# Power_2.net
KiCad netlist of a schematic drawn in Altium Designer
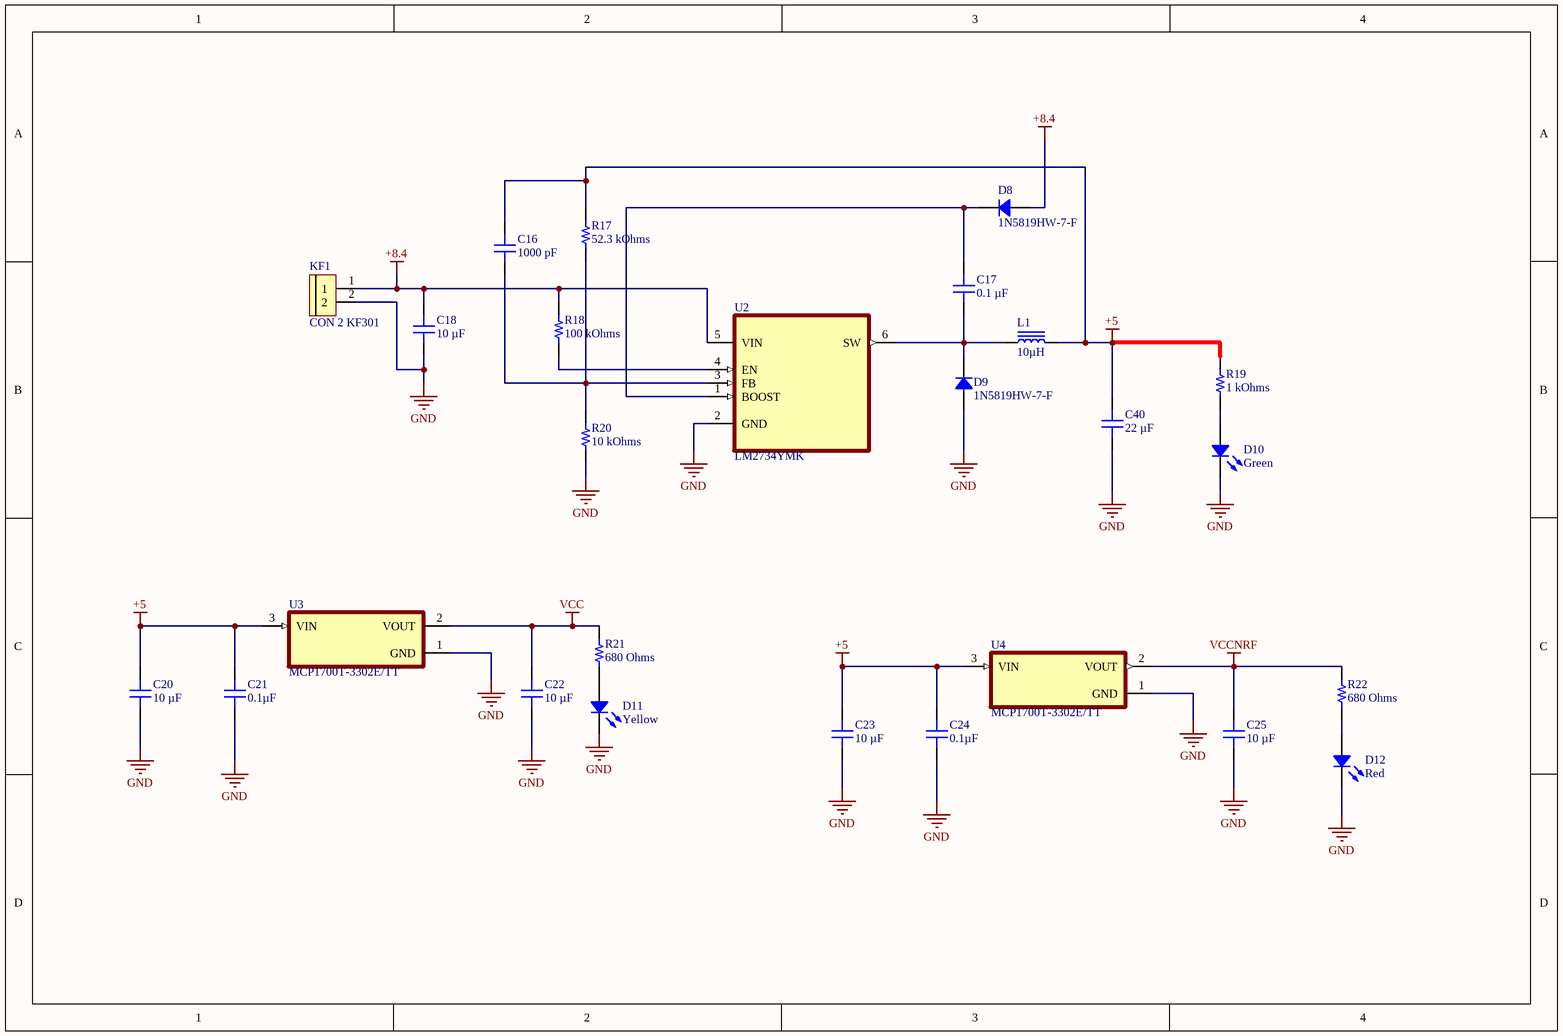
[diagram p0: Power_2.SchDoc]

(export (version "E")
  (design (tool "Eeschema 10.0.6"))
  (components
    (comp (ref "C16")
      (value "1000 pF")
      (footprint "CAP 0603_1608")
      (description "CAP CER 1000PF 10V X7R 0603")
      (fields
        (field (name "PART NUMBER") "VJ0603Y102KXQCW1BC")
        (field (name "MANUFACTURER") "Vishay Vitramon")
      )
      (libsource (lib "Celestial Altium Library - altium_library") (part "Capacitor"))
    )
    (comp (ref "C17")
      (value "0.1 µF")
      (footprint "CAP 0603_1608")
      (description "CAP CER 0.1UF 10V X7R 0603")
      (fields
        (field (name "PART NUMBER") "CX0603MRX7R6BB104")
        (field (name "MANUFACTURER") "PulseLarsen Antennas")
      )
      (libsource (lib "Celestial Altium Library - altium_library") (part "Capacitor"))
    )
    (comp (ref "C18")
      (value "10 µF")
      (footprint "CAP 0805_2012")
      (description "CAP CER 10UF 16V X5R 0805")
      (fields
        (field (name "PART NUMBER") "CL21A106KOQNNWE")
        (field (name "MANUFACTURER") "Samsung Electro-Mechanics")
      )
      (libsource (lib "Celestial Altium Library - altium_library") (part "Capacitor"))
    )
    (comp (ref "C20")
      (value "10 µF")
      (footprint "CAP 0805_2012")
      (description "CAP CER 10UF 16V X5R 0805")
      (fields
        (field (name "PART NUMBER") "CL21A106KOQNNNG")
        (field (name "MANUFACTURER") "Samsung Electro-Mechanics")
      )
      (libsource (lib "Celestial Altium Library - altium_library") (part "Capacitor"))
    )
    (comp (ref "C21")
      (value "0.1µF")
      (footprint "CAP 0603_1608")
      (description "CAP CER 0.1UF 10V X7R 0603")
      (fields (field (name "PART NUMBER") "LD03ZC104KAB2A") (field (name "MANUFACTURER") "AVX Corporation"))
      (libsource (lib "Celestial Altium Library - altium_library") (part "Capacitor"))
    )
    (comp (ref "C22")
      (value "10 µF")
      (footprint "CAP 0603_1608")
      (description "CAP CER 10UF 10V X6S 0603")
      (fields (field (name "PART NUMBER") "KGM15CS61A106MT") (field (name "MANUFACTURER") "KYOCERA AVX"))
      (libsource (lib "Celestial Altium Library - altium_library") (part "Capacitor"))
    )
    (comp (ref "C23")
      (value "10 µF")
      (footprint "CAP 0805_2012")
      (description "CAP CER 10UF 16V X5R 0805")
      (fields
        (field (name "PART NUMBER") "CL21A106KOQNNNG")
        (field (name "MANUFACTURER") "Samsung Electro-Mechanics")
      )
      (libsource (lib "Celestial Altium Library - altium_library") (part "Capacitor"))
    )
    (comp (ref "C24")
      (value "0.1µF")
      (footprint "CAP 0603_1608")
      (description "CAP CER 0.1UF 16V X7R 0603")
      (fields (field (name "PART NUMBER") "0603YC104JAZ2A") (field (name "MANUFACTURER") "AVX Corporation"))
      (libsource (lib "Celestial Altium Library - altium_library") (part "Capacitor"))
    )
    (comp (ref "C25")
      (value "10 µF")
      (footprint "CAP 0603_1608")
      (description "CAP CER 10UF 10V X6S 0603")
      (fields (field (name "PART NUMBER") "KGM15CS61A106MT") (field (name "MANUFACTURER") "KYOCERA AVX"))
      (libsource (lib "Celestial Altium Library - altium_library") (part "Capacitor"))
    )
    (comp (ref "C40")
      (value "22 µF")
      (footprint "CAP 0805_2012")
      (description "CAP CER 22UF 10V X5R 0805")
      (fields
        (field (name "PART NUMBER") "C2012X5R1A226M125AE")
        (field (name "MANUFACTURER") "TDK Corporation")
      )
      (libsource (lib "Celestial Altium Library - altium_library") (part "Capacitor"))
    )
    (comp (ref "D8")
      (value "1N5819HW-7-F")
      (footprint "SOD-123")
      (description "DIODE SCHOTTKY 40V 1A SOD123")
      (fields (field (name "MANUFACTURER") "Diodes Incorporated"))
      (libsource (lib "Celestial Altium Library - altium_library") (part "Diode"))
    )
    (comp (ref "D9")
      (value "1N5819HW-7-F")
      (footprint "SOD-123")
      (description "DIODE SCHOTTKY 40V 1A SOD123")
      (fields (field (name "MANUFACTURER") "Diodes Incorporated"))
      (libsource (lib "Celestial Altium Library - altium_library") (part "Diode"))
    )
    (comp (ref "D10")
      (value "Green")
      (footprint "LED 0603_1608 GREEN")
      (description "LED GREEN CLEAR 0603 SMD")
      (fields (field (name "PART NUMBER") "QBLP601-IG") (field (name "MANUFACTURER") "QT Brightek (QTB)"))
      (libsource (lib "Celestial Altium Library - altium_library") (part "LED"))
    )
    (comp (ref "D11")
      (value "Yellow")
      (footprint "LED 0603_1608 YELLOW")
      (description "LED YELLOW CLEAR 0603 SMD")
      (fields
        (field (name "PART NUMBER") "VAOL-S6YP4")
        (field (name "MANUFACTURER") "Visual Communications Company - VCC")
      )
      (libsource (lib "Celestial Altium Library - altium_library") (part "LED"))
    )
    (comp (ref "D12")
      (value "Red")
      (footprint "LED 0603_1608 RED")
      (description "LED RED CLEAR 0603 SMD")
      (fields
        (field (name "PART NUMBER") "B18W1URO-20C000114U1930")
        (field (name "MANUFACTURER") "Harvatek Corporation")
      )
      (libsource (lib "Celestial Altium Library - altium_library") (part "LED"))
    )
    (comp (ref "KF1")
      (value "CON 2 KF301")
      (footprint "Con 2 KF301 5.08")
      (description "Cắm")
      (libsource (lib "Connector") (part "CON 2 KF301"))
    )
    (comp (ref "L1")
      (value "10µH")
      (footprint "TDK SLF7032")
      (description "FIXED IND 10UH 1.4A 63.6 MOHM")
      (fields
        (field (name "PART NUMBER") "SLF7032T-100M1R4-2PF")
        (field (name "MANUFACTURER") "TDK Corporation")
      )
      (libsource (lib "Celestial Altium Library - altium_library") (part "Inductor"))
    )
    (comp (ref "R17")
      (value "52.3 kOhms")
      (footprint "RES 0603_1608")
      (description "RES 52.3K OHM 1% 1/10W 0603")
      (fields
        (field (name "PART NUMBER") "RMEF0603FT52K3")
        (field (name "MANUFACTURER") "Stackpole Electronics Inc")
      )
      (libsource (lib "Celestial Altium Library - altium_library") (part "Resistor"))
    )
    (comp (ref "R18")
      (value "100 kOhms")
      (footprint "RES 0603_1608")
      (description "RES 100K OHM 0.1% 1/10W 0603")
      (fields (field (name "PART NUMBER") "TNPW0603100KBXEN") (field (name "MANUFACTURER") "Vishay Dale"))
      (libsource (lib "Celestial Altium Library - altium_library") (part "Resistor"))
    )
    (comp (ref "R19")
      (value "1 kOhms")
      (footprint "RES 0603_1608")
      (description "RES SMD 1K OHM 0.1% 1/10W 0603")
      (fields (field (name "PART NUMBER") "RG1608V-102-B-T5") (field (name "MANUFACTURER") "Susumu"))
      (libsource (lib "Celestial Altium Library - altium_library") (part "Resistor"))
    )
    (comp (ref "R20")
      (value "10 kOhms")
      (footprint "RES 0603_1608")
      (description "RES SMD 10K OHM 0.1% 1/16W 0603")
      (fields
        (field (name "PART NUMBER") "CPF-A-0603B10KE1")
        (field (name "MANUFACTURER") "TE Connectivity Passive Product")
      )
      (libsource (lib "Celestial Altium Library - altium_library") (part "Resistor"))
    )
    (comp (ref "R21")
      (value "680 Ohms")
      (footprint "RES 0603_1608")
      (description "RES SMD 680 OHM 0.1% 1/16W 0603")
      (fields
        (field (name "PART NUMBER") "CPF-A-0603B680RE")
        (field (name "MANUFACTURER") "TE Connectivity Passive Product")
      )
      (libsource (lib "Celestial Altium Library - altium_library") (part "Resistor"))
    )
    (comp (ref "R22")
      (value "680 Ohms")
      (footprint "RES 0603_1608")
      (description "RES SMD 680 OHM 0.1% 1/16W 0603")
      (fields
        (field (name "PART NUMBER") "CPF-A-0603B680RE")
        (field (name "MANUFACTURER") "TE Connectivity Passive Product")
      )
      (libsource (lib "Celestial Altium Library - altium_library") (part "Resistor"))
    )
    (comp (ref "U2")
      (value "LM2734YMK")
      (footprint "SOT95P285X100-6N")
      (description "Buck Switching Regulator IC Positive Adjustable 0.8V 1 Output 1A SOT-23-6 Thin, TSOT-23-6")
      (fields (field (name "MF") "Texas Instruments"))
      (libsource (lib "LM2734YMK") (part "LM2734YMK"))
    )
    (comp (ref "U3")
      (value "MCP1700T-3302E/TT")
      (footprint "SOT95P237X112-3N")
      (description "Linear Voltage Regulator IC 1 Output 250mA SOT-23-3")
      (fields (field (name "MF") "Microchip"))
      (libsource (lib "MCP1700T-3302E_TT") (part "MCP1700T-3302E/TT"))
    )
    (comp (ref "U4")
      (value "MCP1700T-3302E/TT")
      (footprint "SOT95P237X112-3N")
      (description "Linear Voltage Regulator IC 1 Output 250mA SOT-23-3")
      (fields (field (name "MF") "Microchip"))
      (libsource (lib "MCP1700T-3302E_TT") (part "MCP1700T-3302E/TT"))
    )
  )
  (nets
    (net (code "1") (name "+5") (class "Default")
      (node (ref "C16") (pin "2") (pinfunction "2_2") (pintype "passive"))
      (node (ref "C20") (pin "2") (pinfunction "2_2") (pintype "passive"))
      (node (ref "C21") (pin "2") (pinfunction "2_2") (pintype "passive"))
      (node (ref "C23") (pin "2") (pinfunction "2_2") (pintype "passive"))
      (node (ref "C24") (pin "2") (pinfunction "2_2") (pintype "passive"))
      (node (ref "C40") (pin "2") (pinfunction "2_2") (pintype "passive"))
      (node (ref "L1") (pin "2") (pinfunction "2_2") (pintype "passive"))
      (node (ref "R17") (pin "2") (pinfunction "2_2") (pintype "passive"))
      (node (ref "R19") (pin "2") (pinfunction "2_2") (pintype "passive"))
      (node (ref "U3") (pin "3") (pinfunction "VIN_3") (pintype "input"))
      (node (ref "U4") (pin "3") (pinfunction "VIN_3") (pintype "input"))
    )
    (net (code "2") (name "+8.4") (class "Default")
      (node (ref "C18") (pin "2") (pinfunction "2_2") (pintype "passive"))
      (node (ref "D8") (pin "1") (pinfunction "1_1") (pintype "passive"))
      (node (ref "KF1") (pin "1") (pinfunction "1_1") (pintype "passive"))
      (node (ref "R18") (pin "2") (pinfunction "2_2") (pintype "passive"))
      (node (ref "U2") (pin "5") (pinfunction "VIN_5") (pintype "power_in"))
    )
    (net (code "3") (name "GND") (class "Default")
      (node (ref "C18") (pin "1") (pinfunction "1_1") (pintype "passive"))
      (node (ref "C20") (pin "1") (pinfunction "1_1") (pintype "passive"))
      (node (ref "C21") (pin "1") (pinfunction "1_1") (pintype "passive"))
      (node (ref "C22") (pin "1") (pinfunction "1_1") (pintype "passive"))
      (node (ref "C23") (pin "1") (pinfunction "1_1") (pintype "passive"))
      (node (ref "C24") (pin "1") (pinfunction "1_1") (pintype "passive"))
      (node (ref "C25") (pin "1") (pinfunction "1_1") (pintype "passive"))
      (node (ref "C40") (pin "1") (pinfunction "1_1") (pintype "passive"))
      (node (ref "D10") (pin "2") (pinfunction "2_2") (pintype "passive"))
      (node (ref "D11") (pin "2") (pinfunction "2_2") (pintype "passive"))
      (node (ref "D12") (pin "2") (pinfunction "2_2") (pintype "passive"))
      (node (ref "D9") (pin "1") (pinfunction "1_1") (pintype "passive"))
      (node (ref "KF1") (pin "2") (pinfunction "2_2") (pintype "passive"))
      (node (ref "R20") (pin "1") (pinfunction "1_1") (pintype "passive"))
      (node (ref "U2") (pin "2") (pinfunction "GND_2") (pintype "passive"))
      (node (ref "U3") (pin "1") (pinfunction "GND_1") (pintype "power_in"))
      (node (ref "U4") (pin "1") (pinfunction "GND_1") (pintype "power_in"))
    )
    (net (code "4") (name "Net-(D10-Pad1)") (class "Default")
      (node (ref "D10") (pin "1") (pinfunction "1_1") (pintype "passive"))
      (node (ref "R19") (pin "1") (pinfunction "1_1") (pintype "passive"))
    )
    (net (code "5") (name "Net-(D11-Pad1)") (class "Default")
      (node (ref "D11") (pin "1") (pinfunction "1_1") (pintype "passive"))
      (node (ref "R21") (pin "1") (pinfunction "1_1") (pintype "passive"))
    )
    (net (code "6") (name "Net-(D12-Pad1)") (class "Default")
      (node (ref "D12") (pin "1") (pinfunction "1_1") (pintype "passive"))
      (node (ref "R22") (pin "1") (pinfunction "1_1") (pintype "passive"))
    )
    (net (code "7") (name "Net-(U2-BOOST)") (class "Default")
      (node (ref "C17") (pin "2") (pinfunction "2_2") (pintype "passive"))
      (node (ref "D8") (pin "2") (pinfunction "2_2") (pintype "passive"))
      (node (ref "U2") (pin "1") (pinfunction "BOOST_1") (pintype "input"))
    )
    (net (code "8") (name "Net-(U2-EN)") (class "Default")
      (node (ref "R18") (pin "1") (pinfunction "1_1") (pintype "passive"))
      (node (ref "U2") (pin "4") (pinfunction "EN_4") (pintype "input"))
    )
    (net (code "9") (name "Net-(U2-FB)") (class "Default")
      (node (ref "C16") (pin "1") (pinfunction "1_1") (pintype "passive"))
      (node (ref "R17") (pin "1") (pinfunction "1_1") (pintype "passive"))
      (node (ref "R20") (pin "2") (pinfunction "2_2") (pintype "passive"))
      (node (ref "U2") (pin "3") (pinfunction "FB_3") (pintype "input"))
    )
    (net (code "10") (name "Net-(U2-SW)") (class "Default")
      (node (ref "C17") (pin "1") (pinfunction "1_1") (pintype "passive"))
      (node (ref "D9") (pin "2") (pinfunction "2_2") (pintype "passive"))
      (node (ref "L1") (pin "1") (pinfunction "1_1") (pintype "passive"))
      (node (ref "U2") (pin "6") (pinfunction "SW_6") (pintype "output"))
    )
    (net (code "11") (name "VCC") (class "Default")
      (node (ref "C22") (pin "2") (pinfunction "2_2") (pintype "passive"))
      (node (ref "R21") (pin "2") (pinfunction "2_2") (pintype "passive"))
      (node (ref "U3") (pin "2") (pinfunction "VOUT_2") (pintype "power_in"))
    )
    (net (code "12") (name "VCCNRF") (class "Default")
      (node (ref "C25") (pin "2") (pinfunction "2_2") (pintype "passive"))
      (node (ref "R22") (pin "2") (pinfunction "2_2") (pintype "passive"))
      (node (ref "U4") (pin "2") (pinfunction "VOUT_2") (pintype "power_in"))
    )
  )
)
